# STM32F103C8T6-V2_0.net
KiCad netlist of a schematic drawn in EasyEDA Pro
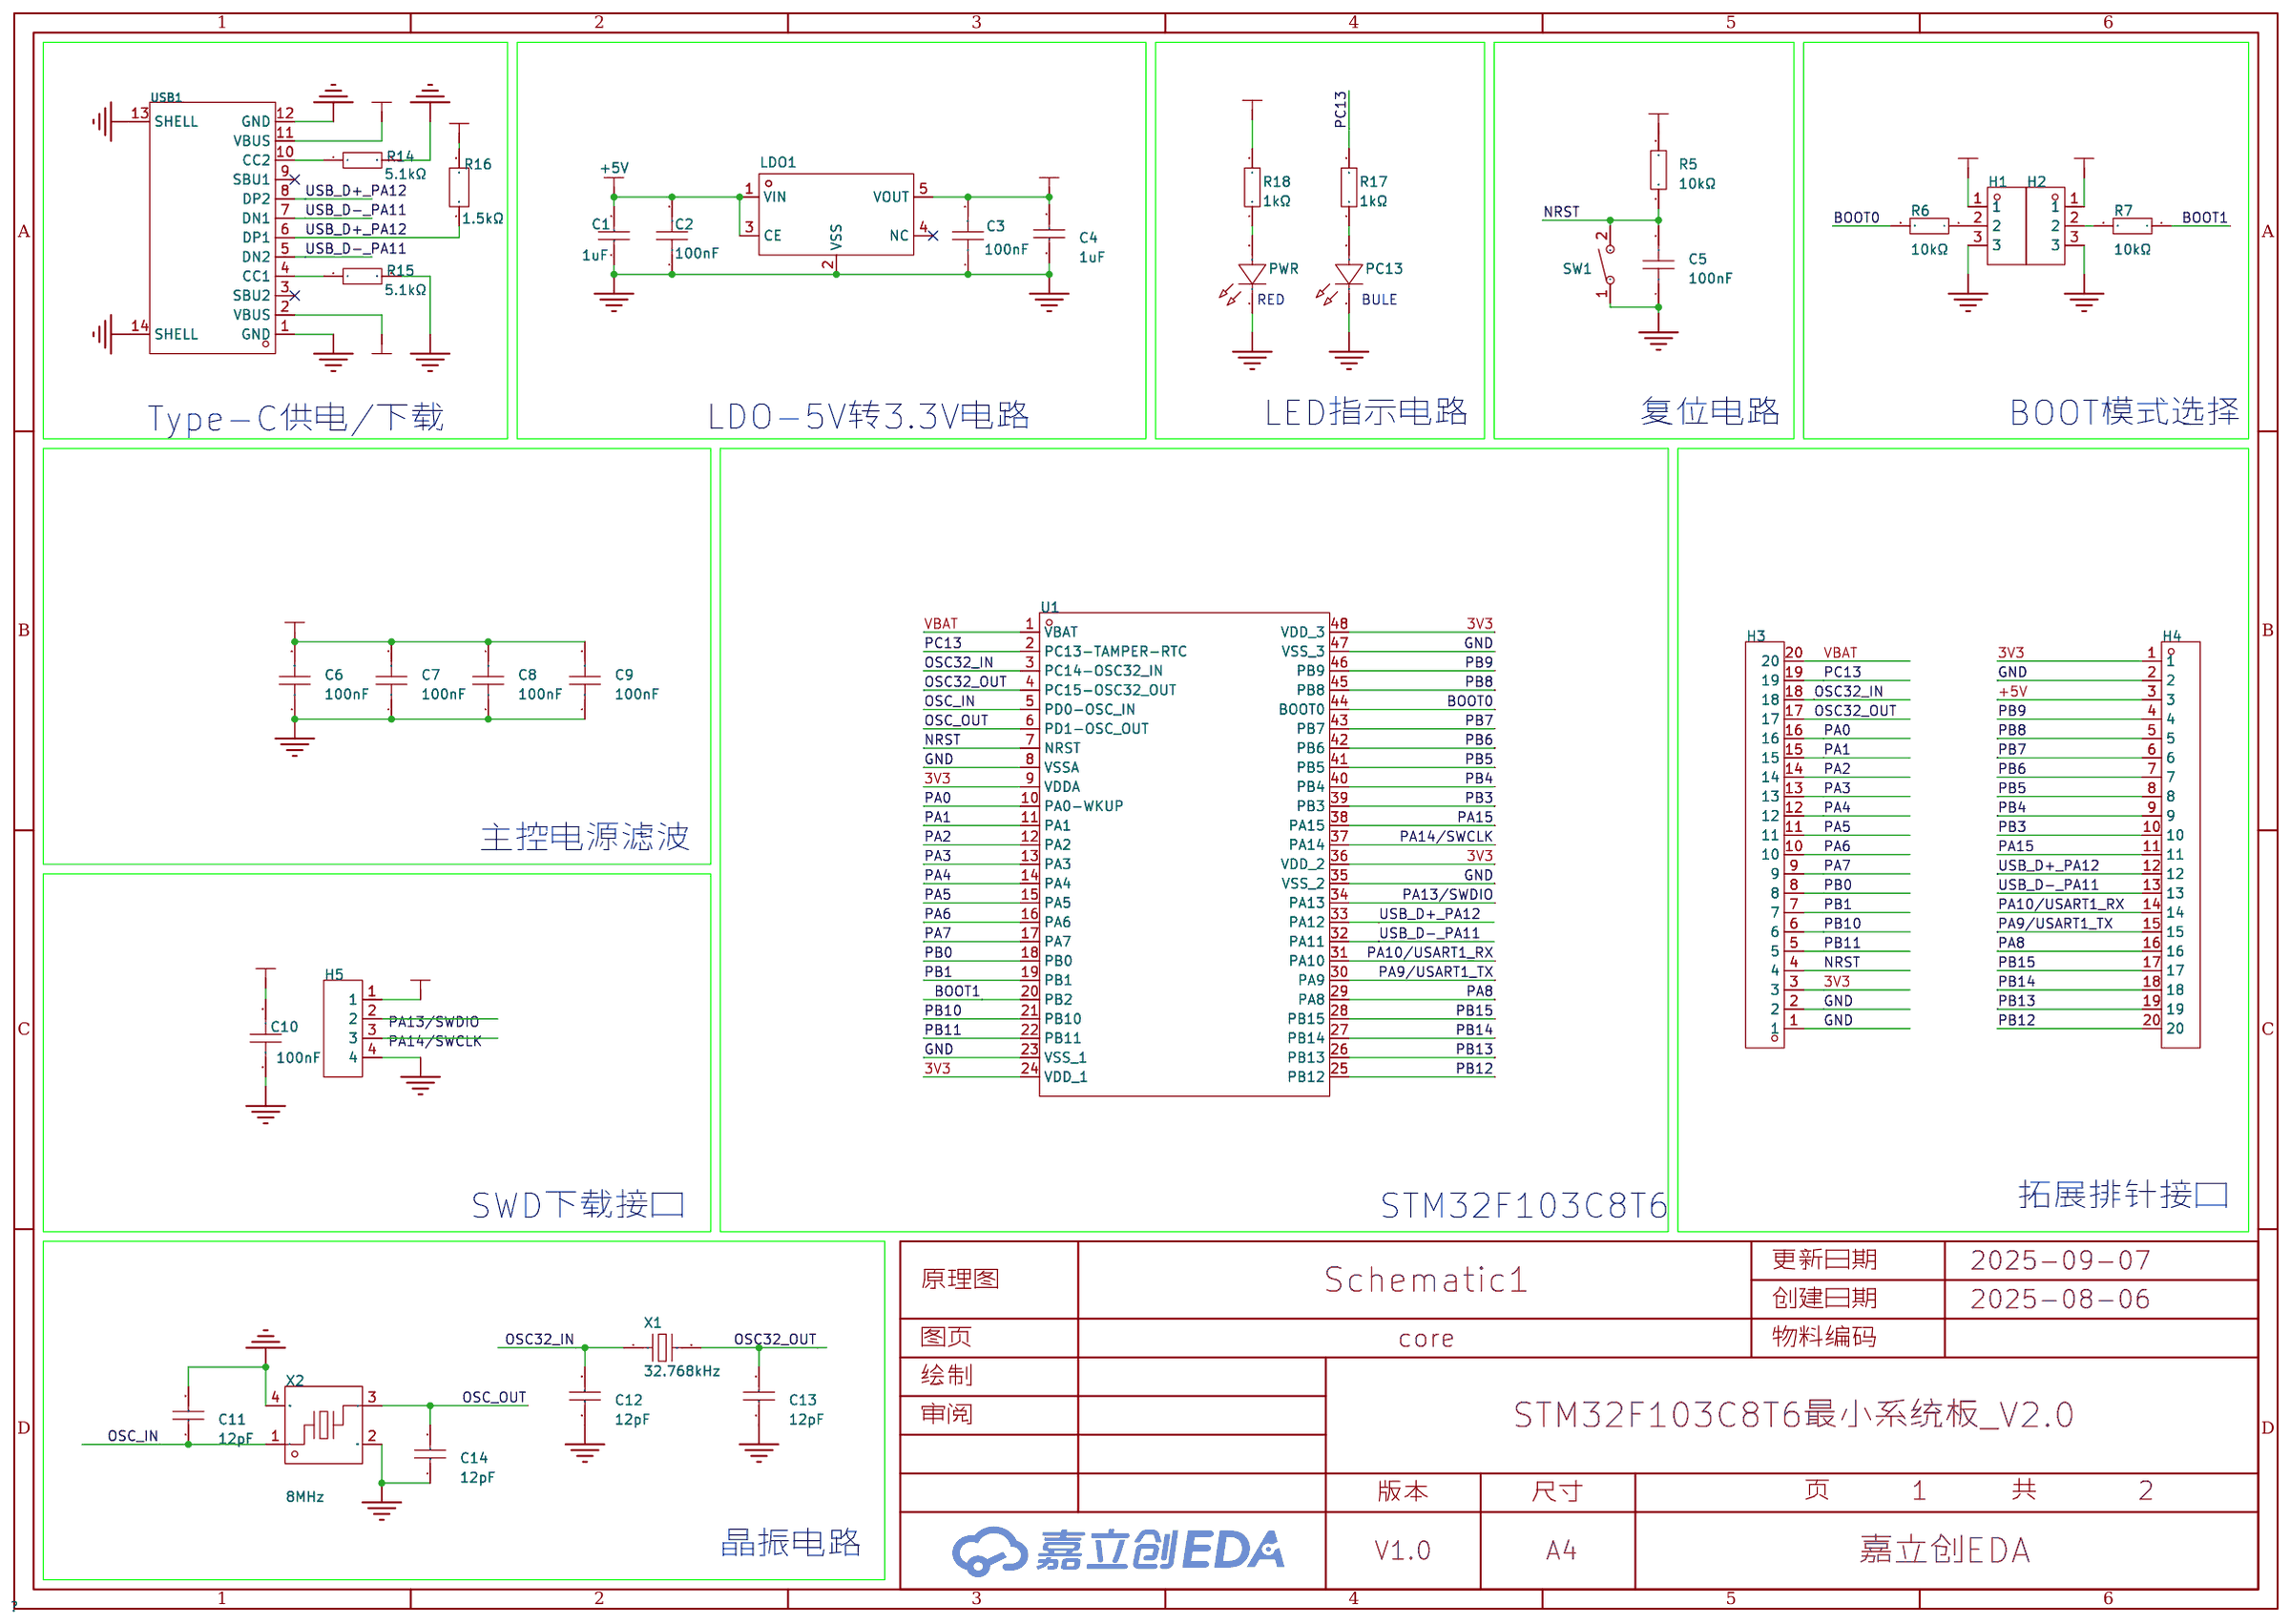
[diagram p0: core]
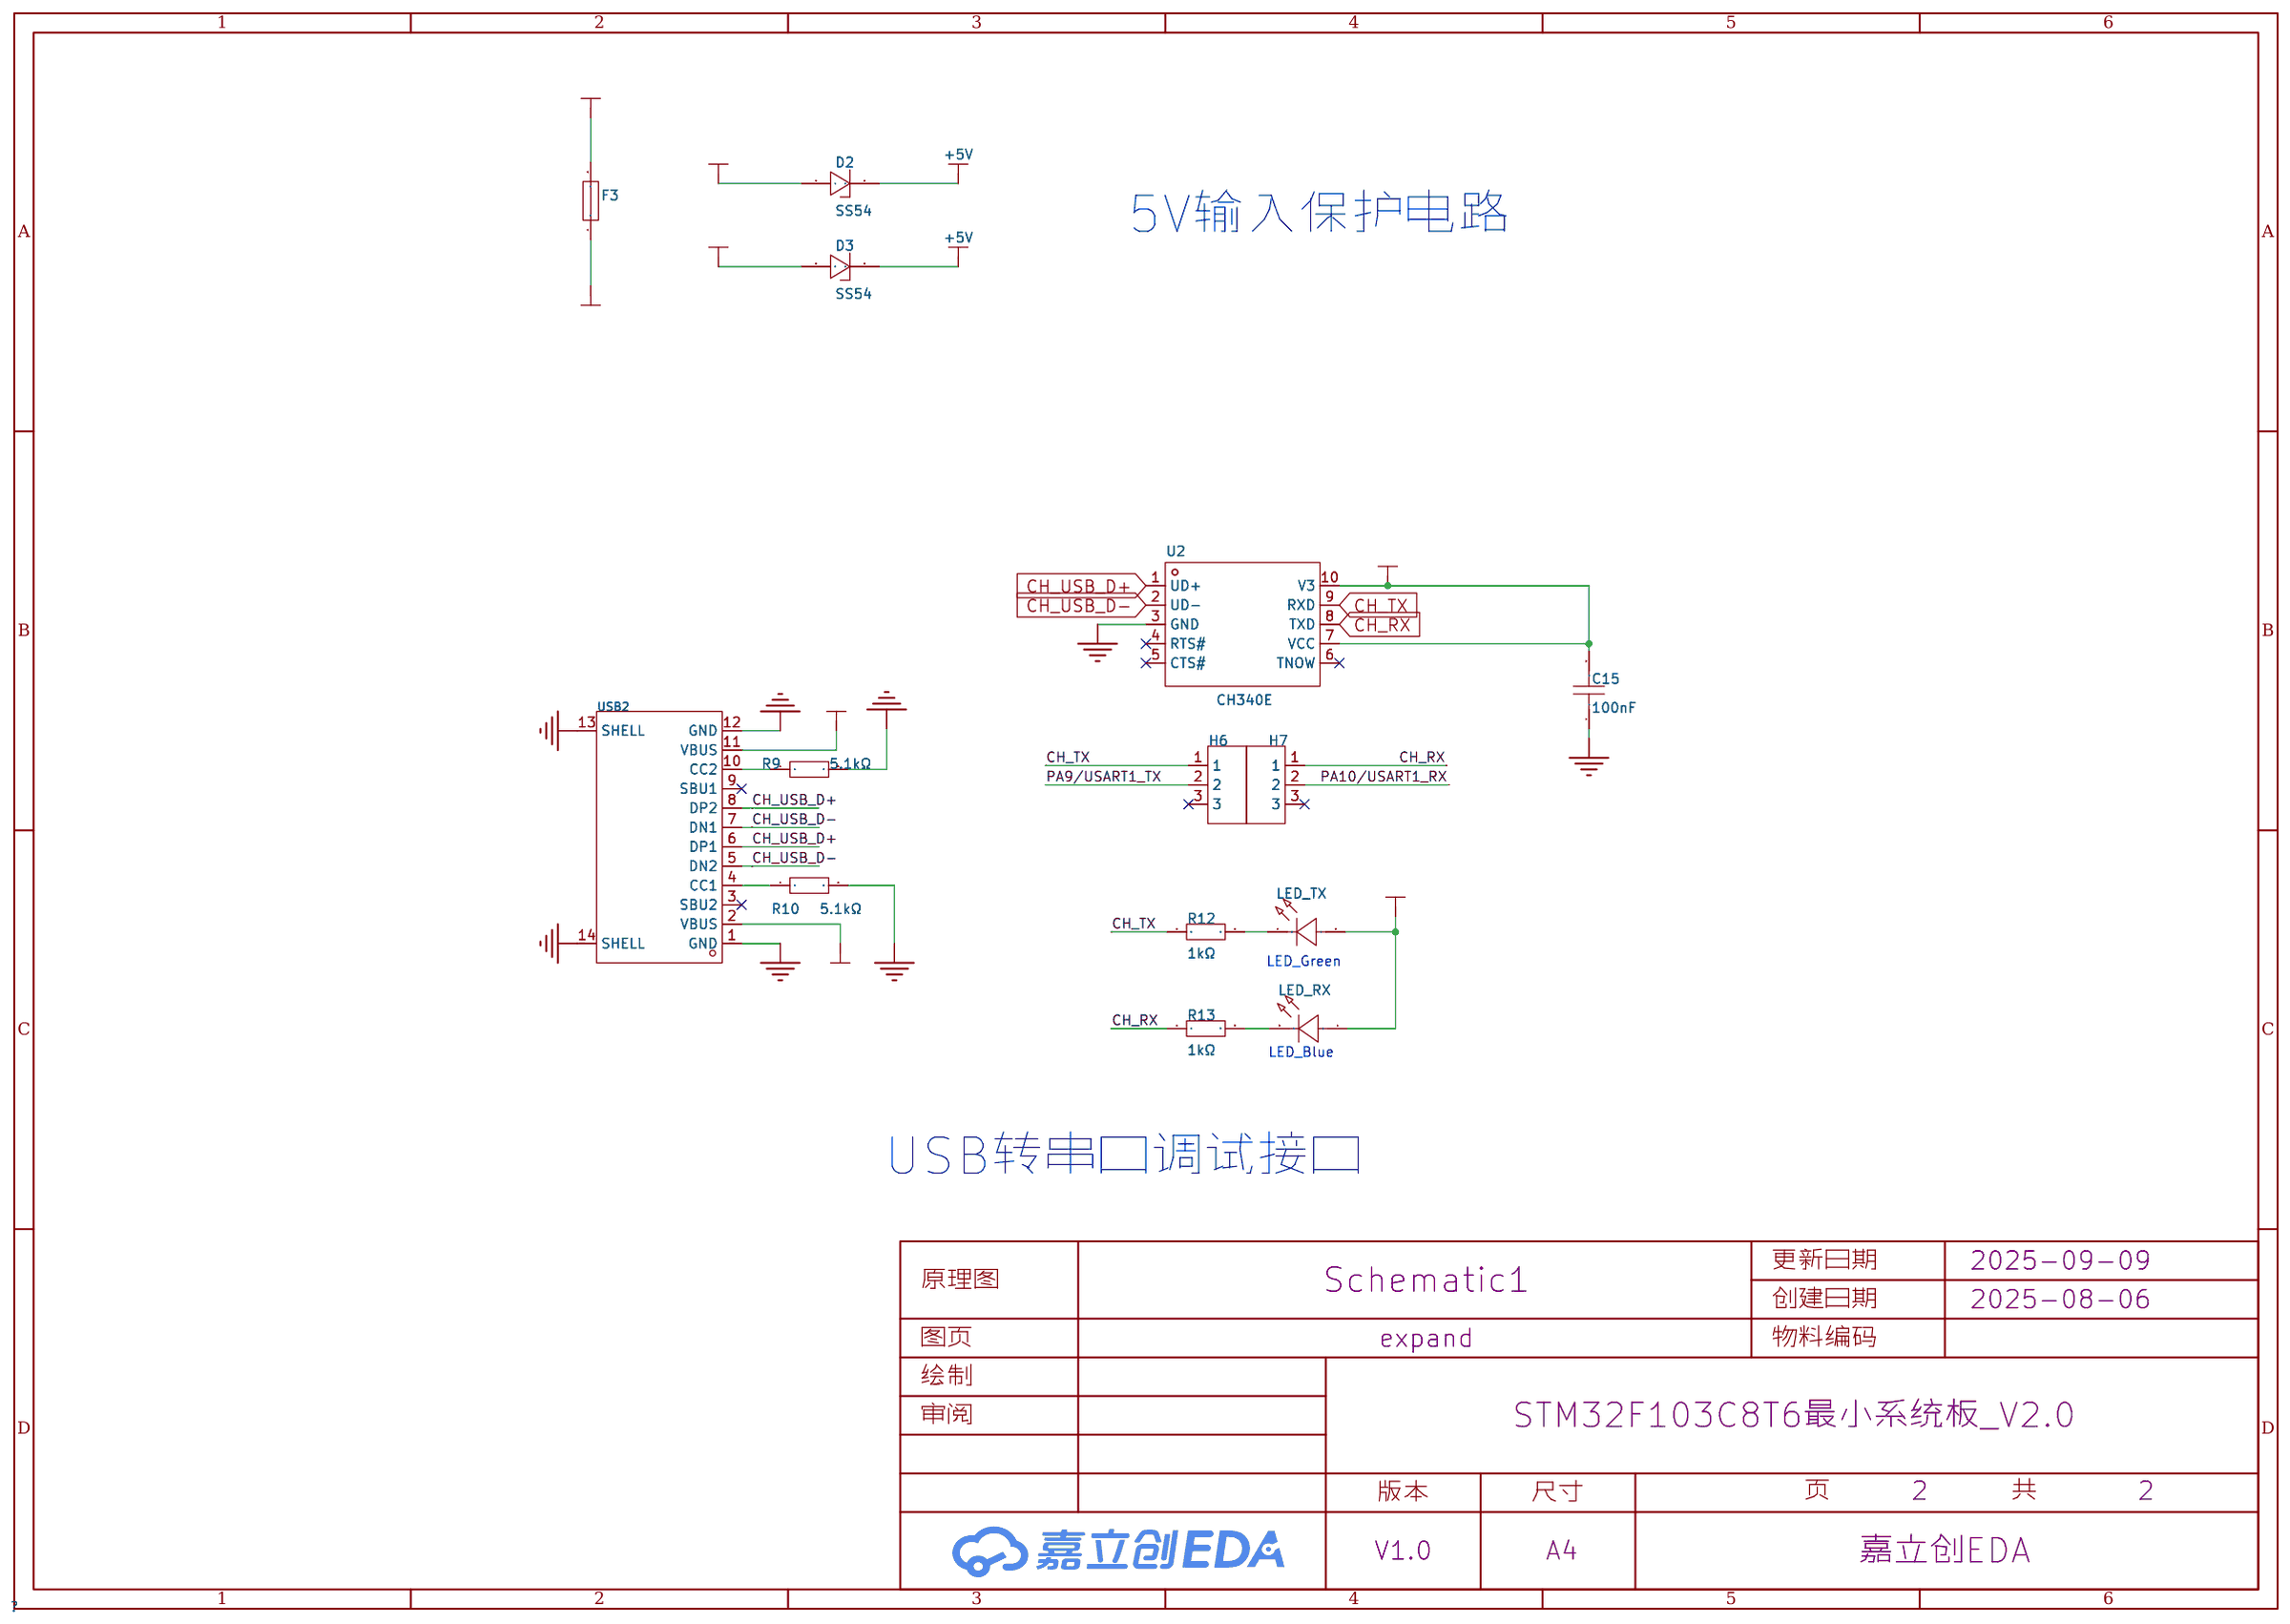
[diagram p1: expand]

(export (version "E")
  (design (tool "Eeschema 10.0.6"))
  (components
    (comp (ref "C1")
      (value "1uF")
      (footprint "easyedapro:C0402")
      (description "容值:1uF;精度:±10%;额定电压:10V;材质(温度系数):X5R;")
      (fields
        (field (name "Manufacturer Part") "CL21B105KBFNNNE")
        (field (name "Manufacturer") "SAMSUNG(三星)")
      )
      (libsource (lib "easyedapro") (part "CL05A105KP5NNNC"))
    )
    (comp (ref "C2")
      (value "100nF")
      (footprint "easyedapro:C0402")
      (description "容值:100nF;精度:±10%;额定电压:50V;材质(温度系数):X7R;")
      (fields
        (field (name "Manufacturer Part") "CC0805KRX7R9BB104")
        (field (name "Manufacturer") "YAGEO(国巨)")
      )
      (libsource (lib "easyedapro") (part "GRM155R71H104KE14D"))
    )
    (comp (ref "C3")
      (value "100nF")
      (footprint "easyedapro:C0402")
      (description "容值:100nF;精度:±10%;额定电压:50V;材质(温度系数):X7R;")
      (fields
        (field (name "Manufacturer Part") "CC0805KRX7R9BB104")
        (field (name "Manufacturer") "YAGEO(国巨)")
      )
      (libsource (lib "easyedapro") (part "GRM155R71H104KE14D"))
    )
    (comp (ref "C4")
      (value "1uF")
      (footprint "easyedapro:C0402")
      (description "容值:1uF;精度:±10%;额定电压:10V;材质(温度系数):X5R;")
      (fields
        (field (name "Manufacturer Part") "CL21B105KBFNNNE")
        (field (name "Manufacturer") "SAMSUNG(三星)")
      )
      (libsource (lib "easyedapro") (part "CL05A105KP5NNNC"))
    )
    (comp (ref "C5")
      (value "100nF")
      (footprint "easyedapro:C0402")
      (description "容值:100nF;精度:±10%;额定电压:50V;材质(温度系数):X7R;")
      (fields
        (field (name "Manufacturer Part") "CC0805KRX7R9BB104")
        (field (name "Manufacturer") "YAGEO(国巨)")
      )
      (libsource (lib "easyedapro") (part "GRM155R71H104KE14D"))
    )
    (comp (ref "C6")
      (value "100nF")
      (footprint "easyedapro:C0402")
      (description "容值:100nF;精度:±10%;额定电压:50V;材质(温度系数):X7R;")
      (fields
        (field (name "Manufacturer Part") "CC0805KRX7R9BB104")
        (field (name "Manufacturer") "YAGEO(国巨)")
      )
      (libsource (lib "easyedapro") (part "GRM155R71H104KE14D"))
    )
    (comp (ref "C7")
      (value "100nF")
      (footprint "easyedapro:C0402")
      (description "容值:100nF;精度:±10%;额定电压:50V;材质(温度系数):X7R;")
      (fields
        (field (name "Manufacturer Part") "CC0805KRX7R9BB104")
        (field (name "Manufacturer") "YAGEO(国巨)")
      )
      (libsource (lib "easyedapro") (part "GRM155R71H104KE14D"))
    )
    (comp (ref "C8")
      (value "100nF")
      (footprint "easyedapro:C0402")
      (description "容值:100nF;精度:±10%;额定电压:50V;材质(温度系数):X7R;")
      (fields
        (field (name "Manufacturer Part") "CC0805KRX7R9BB104")
        (field (name "Manufacturer") "YAGEO(国巨)")
      )
      (libsource (lib "easyedapro") (part "GRM155R71H104KE14D"))
    )
    (comp (ref "C9")
      (value "100nF")
      (footprint "easyedapro:C0402")
      (description "容值:100nF;精度:±10%;额定电压:50V;材质(温度系数):X7R;")
      (fields
        (field (name "Manufacturer Part") "CC0805KRX7R9BB104")
        (field (name "Manufacturer") "YAGEO(国巨)")
      )
      (libsource (lib "easyedapro") (part "GRM155R71H104KE14D"))
    )
    (comp (ref "C10")
      (value "100nF")
      (footprint "easyedapro:C0402")
      (description "容值:100nF;精度:±10%;额定电压:50V;材质(温度系数):X7R;")
      (fields
        (field (name "Manufacturer Part") "CC0805KRX7R9BB104")
        (field (name "Manufacturer") "YAGEO(国巨)")
      )
      (libsource (lib "easyedapro") (part "GRM155R71H104KE14D"))
    )
    (comp (ref "C11")
      (value "12pF")
      (footprint "easyedapro:C0402")
      (description "容值:12pF;精度:±5%;额定电压:50V;材质(温度系数):C0G;")
      (fields (field (name "Manufacturer Part") "0402CG120J500NT") (field (name "Manufacturer") "FH(风华)"))
      (libsource (lib "easyedapro") (part "0402CG120J500NT"))
    )
    (comp (ref "C12")
      (value "12pF")
      (footprint "easyedapro:C0402")
      (description "容值:12pF;精度:±5%;额定电压:50V;材质(温度系数):C0G;")
      (fields (field (name "Manufacturer Part") "0402CG120J500NT") (field (name "Manufacturer") "FH(风华)"))
      (libsource (lib "easyedapro") (part "0402CG120J500NT"))
    )
    (comp (ref "C13")
      (value "12pF")
      (footprint "easyedapro:C0402")
      (description "容值:12pF;精度:±5%;额定电压:50V;材质(温度系数):C0G;")
      (fields (field (name "Manufacturer Part") "0402CG120J500NT") (field (name "Manufacturer") "FH(风华)"))
      (libsource (lib "easyedapro") (part "0402CG120J500NT"))
    )
    (comp (ref "C14")
      (value "12pF")
      (footprint "easyedapro:C0402")
      (description "容值:12pF;精度:±5%;额定电压:50V;材质(温度系数):C0G;")
      (fields (field (name "Manufacturer Part") "0402CG120J500NT") (field (name "Manufacturer") "FH(风华)"))
      (libsource (lib "easyedapro") (part "0402CG120J500NT"))
    )
    (comp (ref "H1")
      (value "PZ254V-11-03P")
      (footprint "easyedapro:HDR-TH_3P-P2.54-V-M")
      (fields (field (name "Manufacturer") "XFCN(兴飞)"))
      (libsource (lib "easyedapro") (part "PZ254V-11-03P_C2937625"))
    )
    (comp (ref "H2")
      (value "PZ254V-11-03P")
      (footprint "easyedapro:HDR-TH_3P-P2.54-V-M")
      (fields (field (name "Manufacturer") "XFCN(兴飞)"))
      (libsource (lib "easyedapro") (part "PZ254V-11-03P_C2937625"))
    )
    (comp (ref "H3")
      (value "PH2.54-01-20PZD")
      (footprint "easyedapro:HDR-TH_20P-P2.54-V-M-1")
      (fields (field (name "Manufacturer") "XUNPU(讯普)"))
      (libsource (lib "easyedapro") (part "HDR_2.54-1x20P"))
    )
    (comp (ref "H4")
      (value "PH2.54-01-20PZD")
      (footprint "easyedapro:HDR-TH_20P-P2.54-V-M-1")
      (fields (field (name "Manufacturer") "XUNPU(讯普)"))
      (libsource (lib "easyedapro") (part "HDR_2.54-1x20P"))
    )
    (comp (ref "H5")
      (value "PZ2.54-1*4-WZ")
      (footprint "easyedapro:HDR-TH_4P-P2.54-H-M-W7.7-P")
      (description "插针结构:1x4P;间距:2.54mm;安装方式:弯插;排数:单排;总PIN位数:4P;触头镀层:金;")
      (fields (field (name "Manufacturer") "ZHOURI(洲日)"))
      (libsource (lib "easyedapro") (part "PZ2.54-1*4-WZ"))
    )
    (comp (ref "LDO1")
      (value "ME6211C33M5G-N")
      (footprint "easyedapro:SOT-23-5_L3.0-W1.7-P0.95-LS2.8-BL")
      (description "输出类型:固定;输出极性:正;最大输入电压:6V;输出电压:3.3V;输出电流:500mA;电源纹波抑制比(PSRR):70dB;")
      (fields (field (name "Manufacturer") "MICRONE(南京微盟)"))
      (libsource (lib "easyedapro") (part "ME6211C33M5G-N"))
    )
    (comp (ref "PC13")
      (value "XL-2012UBC")
      (footprint "easyedapro:LED0805-RD")
      (fields (field (name "Manufacturer") "XINGLIGHT(成兴光)"))
      (libsource (lib "easyedapro") (part "XL-2012UBC"))
    )
    (comp (ref "PWR")
      (value "XL-2012SURC")
      (footprint "easyedapro:LED0805-RD_RED")
      (description "发光颜色:红色;功率:55mW;正向电流:25mA;主波长:617nm~621nm;透镜颜色:无色透明透镜;色温:-;发光角度:120°;载带方式:正贴;工作温度:-30°C~+85°C;")
      (fields (field (name "Manufacturer") "XINGLIGHT(成兴光)"))
      (libsource (lib "easyedapro") (part "XL-2012SURC"))
    )
    (comp (ref "R5")
      (value "10kΩ")
      (footprint "easyedapro:R0402")
      (description "电阻类型:厚膜电阻;阻值:10kΩ;精度:±1%;功率:62.5mW;最大工作电压:50V;温度系数:±100ppm/°C;")
      (fields
        (field (name "Manufacturer Part") "0805W8F1002T5E")
        (field (name "Manufacturer") "UNI-ROYAL(厚声)")
      )
      (libsource (lib "easyedapro") (part "RC0402FR-0710KL"))
    )
    (comp (ref "R6")
      (value "10kΩ")
      (footprint "easyedapro:R0402")
      (description "电阻类型:厚膜电阻;阻值:10kΩ;精度:±1%;功率:62.5mW;最大工作电压:50V;温度系数:±100ppm/°C;")
      (fields
        (field (name "Manufacturer Part") "0805W8F1002T5E")
        (field (name "Manufacturer") "UNI-ROYAL(厚声)")
      )
      (libsource (lib "easyedapro") (part "RC0402FR-0710KL"))
    )
    (comp (ref "R7")
      (value "10kΩ")
      (footprint "easyedapro:R0402")
      (description "电阻类型:厚膜电阻;阻值:10kΩ;精度:±1%;功率:62.5mW;最大工作电压:50V;温度系数:±100ppm/°C;")
      (fields
        (field (name "Manufacturer Part") "0805W8F1002T5E")
        (field (name "Manufacturer") "UNI-ROYAL(厚声)")
      )
      (libsource (lib "easyedapro") (part "RC0402FR-0710KL"))
    )
    (comp (ref "R14")
      (value "5.1kΩ")
      (footprint "easyedapro:R0805")
      (description "电阻类型:厚膜电阻;阻值:5.1kΩ;精度:±1%;功率:125mW;最大工作电压:150V;温度系数:±100ppm/°C;")
      (fields
        (field (name "Manufacturer Part") "0805W8F5101T5E")
        (field (name "Manufacturer") "UNI-ROYAL(厚声)")
      )
      (libsource (lib "easyedapro") (part "0805W8F5101T5E"))
    )
    (comp (ref "R15")
      (value "5.1kΩ")
      (footprint "easyedapro:R0805")
      (description "电阻类型:厚膜电阻;阻值:5.1kΩ;精度:±1%;功率:125mW;最大工作电压:150V;温度系数:±100ppm/°C;")
      (fields
        (field (name "Manufacturer Part") "0805W8F5101T5E")
        (field (name "Manufacturer") "UNI-ROYAL(厚声)")
      )
      (libsource (lib "easyedapro") (part "0805W8F5101T5E"))
    )
    (comp (ref "R16")
      (value "1.5kΩ")
      (footprint "easyedapro:R0805")
      (description "电阻类型:厚膜电阻;阻值:1.5kΩ;精度:±1%;功率:125mW;工作电压:150V;温度系数:±100ppm/°C;")
      (fields (field (name "Manufacturer Part") "FRC0805F1501TS") (field (name "Manufacturer") "FOJAN(富捷)"))
      (libsource (lib "easyedapro") (part "FRC0805F1501TS"))
    )
    (comp (ref "R17")
      (value "1kΩ")
      (footprint "easyedapro:R0805")
      (description "电阻类型:厚膜电阻;阻值:1kΩ;精度:±1%;功率:125mW;最大工作电压:150V;温度系数:±100ppm/°C;")
      (fields
        (field (name "Manufacturer Part") "0805W8F1001T5E")
        (field (name "Manufacturer") "UNI-ROYAL(厚声)")
      )
      (libsource (lib "easyedapro") (part "0805W8F1001T5E"))
    )
    (comp (ref "R18")
      (value "1kΩ")
      (footprint "easyedapro:R0805")
      (description "电阻类型:厚膜电阻;阻值:1kΩ;精度:±1%;功率:125mW;最大工作电压:150V;温度系数:±100ppm/°C;")
      (fields
        (field (name "Manufacturer Part") "0805W8F1001T5E")
        (field (name "Manufacturer") "UNI-ROYAL(厚声)")
      )
      (libsource (lib "easyedapro") (part "0805W8F1001T5E"))
    )
    (comp (ref "SW1")
      (value "TS-1101-B-W")
      (footprint "easyedapro:KEY-SMD_2P-L6.0-W3.6-P7.4-LS8.0-L")
      (description "触点电流:50mA;额定电压(DC):12V;绝缘电阻:-;电路结构:单刀单掷;安装方式:立贴;带灯:无;作用力:160gf;机械寿命:5万次;带支架:否;")
      (fields (field (name "Manufacturer") "XKB Connectivity(中国星坤)"))
      (libsource (lib "easyedapro") (part "TS-1101-B-W"))
    )
    (comp (ref "U1")
      (value "STM32F103C8T6")
      (fields (field (name "Manufacturer") "ST(意法半导体)"))
      (libsource (lib "easyedapro") (part "STM32F103C8T6"))
    )
    (comp (ref "USB1")
      (value "TYPE-C 16PIN 2MD(073)")
      (footprint "easyedapro:USB-C-SMD_TYPE-C-6PIN-2MD-073")
      (description "连接器类型:Type-C;标准:-;公母:母座;触点数量:16;端口数量:1;安装方式:卧贴;额定电流 - 电源:5A;工作温度范围:-25°C~+85°C;")
      (fields (field (name "Manufacturer") "SHOU HAN(首韩)"))
      (libsource (lib "easyedapro") (part "TYPE-C 16PIN 2MD(073)"))
    )
    (comp (ref "X1")
      (value "32.768kHz")
      (footprint "easyedapro:OSC-SMD_L3.2-W1.5")
      (description "晶振类型:贴片晶振;频率:32.768kHz;常温频差:±20ppm;外接负载电容:12.5pF;频率稳定度(全温):-;")
      (fields (field (name "Manufacturer Part") "X321532768KGD2SI") (field (name "Manufacturer") "YXC(扬兴晶振)"))
      (libsource (lib "easyedapro") (part "X321532768KGD2SI"))
    )
    (comp (ref "X2")
      (value "8MHz")
      (footprint "easyedapro:CRYSTAL-SMD_4P-L3.2-W2.5-BL-1")
      (description "晶振类型:贴片晶振;频率:8MHz;常温频差:±10ppm;外接负载电容:12pF;频率稳定度(全温):±20ppm;")
      (fields
        (field (name "Manufacturer Part") "XL2EL89COI-111YLC-8M")
        (field (name "Manufacturer") "YXC(扬兴晶振)")
      )
      (libsource (lib "easyedapro") (part "XL2EL89COI-111YLC-8M"))
    )
    (comp (ref "C15")
      (value "100nF")
      (footprint "easyedapro:C0402")
      (description "容值:100nF;精度:±10%;额定电压:50V;材质(温度系数):X7R;")
      (fields
        (field (name "Manufacturer Part") "CC0805KRX7R9BB104")
        (field (name "Manufacturer") "YAGEO(国巨)")
      )
      (libsource (lib "easyedapro") (part "GRM155R71H104KE14D"))
    )
    (comp (ref "D2")
      (value "SS54")
      (footprint "easyedapro:SMA_L4.3-W2.6-LS5.0-FD")
      (description "二极管配置:独立式;正向压降(Vf):550mV@5.0A;直流反向耐压(Vr):40V;整流电流:5A;")
      (fields (field (name "Manufacturer") "R+O(宏嘉诚)"))
      (libsource (lib "easyedapro") (part "SS54_C7420369"))
    )
    (comp (ref "D3")
      (value "SS54")
      (footprint "easyedapro:SMA_L4.3-W2.6-LS5.0-FD")
      (description "二极管配置:独立式;正向压降(Vf):550mV@5.0A;直流反向耐压(Vr):40V;整流电流:5A;")
      (fields (field (name "Manufacturer") "R+O(宏嘉诚)"))
      (libsource (lib "easyedapro") (part "SS54_C7420369"))
    )
    (comp (ref "F3")
      (value "BSMD0805-050-6V")
      (footprint "easyedapro:F0603")
      (description "最大电压:6V;最大电流:40A;保持电流:500mA;跳闸电流:1A;")
      (fields (field (name "Manufacturer") "BHFUSE(佰宏)"))
      (libsource (lib "easyedapro") (part "BSMD0603-050-6V"))
    )
    (comp (ref "H6")
      (value "PZ254V-11-03P")
      (footprint "easyedapro:HDR-TH_3P-P2.54-V-M")
      (fields (field (name "Manufacturer") "XFCN(兴飞)"))
      (libsource (lib "easyedapro") (part "PZ254V-11-03P_C2937625"))
    )
    (comp (ref "H7")
      (value "PZ254V-11-03P")
      (footprint "easyedapro:HDR-TH_3P-P2.54-V-M")
      (fields (field (name "Manufacturer") "XFCN(兴飞)"))
      (libsource (lib "easyedapro") (part "PZ254V-11-03P_C2937625"))
    )
    (comp (ref "LED_RX")
      (value "XL-1608UBC-06A")
      (footprint "easyedapro:LED0603-R-RD")
      (fields (field (name "Manufacturer") "XINGLIGHT(成兴光)"))
      (libsource (lib "easyedapro") (part "XL-1608UBC-06A"))
    )
    (comp (ref "LED_TX")
      (value "XL-1608PGC-06")
      (footprint "easyedapro:LED0603-RD_GREEN")
      (fields (field (name "Manufacturer") "XINGLIGHT(成兴光)"))
      (libsource (lib "easyedapro") (part "XL-1608PGC-06"))
    )
    (comp (ref "R9")
      (value "5.1kΩ")
      (footprint "easyedapro:R0402")
      (description "电阻类型:厚膜电阻;阻值:5.1kΩ;精度:±1%;功率:62.5mW;最大工作电压:50V;温度系数:±100ppm/°C;")
      (fields
        (field (name "Manufacturer Part") "0805W8F5101T5E")
        (field (name "Manufacturer") "UNI-ROYAL(厚声)")
      )
      (libsource (lib "easyedapro") (part "0402WGF5101TCE"))
    )
    (comp (ref "R10")
      (value "5.1kΩ")
      (footprint "easyedapro:R0402")
      (description "电阻类型:厚膜电阻;阻值:5.1kΩ;精度:±1%;功率:62.5mW;最大工作电压:50V;温度系数:±100ppm/°C;")
      (fields
        (field (name "Manufacturer Part") "0805W8F5101T5E")
        (field (name "Manufacturer") "UNI-ROYAL(厚声)")
      )
      (libsource (lib "easyedapro") (part "0402WGF5101TCE"))
    )
    (comp (ref "R12")
      (value "1kΩ")
      (footprint "easyedapro:R0402")
      (description "电阻类型:厚膜电阻;阻值:1kΩ;精度:±1%;功率:62.5mW;最大工作电压:50V;温度系数:±100ppm/°C;")
      (fields
        (field (name "Manufacturer Part") "0805W8F1001T5E")
        (field (name "Manufacturer") "UNI-ROYAL(厚声)")
      )
      (libsource (lib "easyedapro") (part "0402WGF1001TCE"))
    )
    (comp (ref "R13")
      (value "1kΩ")
      (footprint "easyedapro:R0402")
      (description "电阻类型:厚膜电阻;阻值:1kΩ;精度:±1%;功率:62.5mW;最大工作电压:50V;温度系数:±100ppm/°C;")
      (fields
        (field (name "Manufacturer Part") "0805W8F1001T5E")
        (field (name "Manufacturer") "UNI-ROYAL(厚声)")
      )
      (libsource (lib "easyedapro") (part "0402WGF1001TCE"))
    )
    (comp (ref "U2")
      (value "CH340E")
      (footprint "easyedapro:MSOP-10_L3.0-W3.0-P0.50-LS5.0-BL")
      (description "应用功能:收发器;接口协议:USB 2.0;数据速率:2Mbps;")
      (fields (field (name "Manufacturer") "WCH(南京沁恒)"))
      (libsource (lib "easyedapro") (part "CH340E"))
    )
    (comp (ref "USB2")
      (value "TYPE-C 16PIN 2MD(073)")
      (footprint "easyedapro:USB-C-SMD_TYPE-C-6PIN-2MD-073")
      (description "连接器类型:Type-C;标准:-;公母:母座;触点数量:16;端口数量:1;安装方式:卧贴;额定电流 - 电源:5A;工作温度范围:-25°C~+85°C;")
      (fields (field (name "Manufacturer") "SHOU HAN(首韩)"))
      (libsource (lib "easyedapro") (part "TYPE-C 16PIN 2MD(073)"))
    )
  )
  (nets
    (net (code "1") (name "+5V") (class "Default")
      (node (ref "C1") (pin "2") (pinfunction "2_2") (pintype "input"))
      (node (ref "C2") (pin "2") (pinfunction "2_2") (pintype "unspecified"))
      (node (ref "D2") (pin "2") (pinfunction "K_2") (pintype "unspecified"))
      (node (ref "D3") (pin "2") (pinfunction "K_2") (pintype "unspecified"))
      (node (ref "H4") (pin "3") (pinfunction "3_3") (pintype "input"))
      (node (ref "LDO1") (pin "1") (pinfunction "VIN_1") (pintype "input"))
      (node (ref "LDO1") (pin "3") (pinfunction "CE_3") (pintype "input"))
    )
    (net (code "2") (name "3V3") (class "Default")
      (node (ref "C10") (pin "2") (pinfunction "2_2") (pintype "unspecified"))
      (node (ref "C15") (pin "2") (pinfunction "2_2") (pintype "unspecified"))
      (node (ref "C3") (pin "2") (pinfunction "2_2") (pintype "unspecified"))
      (node (ref "C4") (pin "2") (pinfunction "2_2") (pintype "input"))
      (node (ref "C6") (pin "2") (pinfunction "2_2") (pintype "unspecified"))
      (node (ref "C7") (pin "2") (pinfunction "2_2") (pintype "unspecified"))
      (node (ref "C8") (pin "2") (pinfunction "2_2") (pintype "unspecified"))
      (node (ref "C9") (pin "2") (pinfunction "2_2") (pintype "unspecified"))
      (node (ref "H1") (pin "1") (pinfunction "1_1") (pintype "input"))
      (node (ref "H2") (pin "1") (pinfunction "1_1") (pintype "input"))
      (node (ref "H3") (pin "3") (pinfunction "3_3") (pintype "input"))
      (node (ref "H4") (pin "1") (pinfunction "1_1") (pintype "input"))
      (node (ref "H5") (pin "1") (pinfunction "1_1") (pintype "unspecified"))
      (node (ref "LDO1") (pin "5") (pinfunction "VOUT_5") (pintype "input"))
      (node (ref "LED_RX") (pin "1") (pinfunction "A_1") (pintype "unspecified"))
      (node (ref "LED_TX") (pin "2") (pinfunction "A_2") (pintype "unspecified"))
      (node (ref "R16") (pin "2") (pinfunction "2_2") (pintype "unspecified"))
      (node (ref "R18") (pin "2") (pinfunction "2_2") (pintype "input"))
      (node (ref "R5") (pin "2") (pinfunction "2_2") (pintype "input"))
      (node (ref "U1") (pin "24") (pinfunction "VDD_1_24") (pintype "unspecified"))
      (node (ref "U1") (pin "36") (pinfunction "VDD_2_36") (pintype "unspecified"))
      (node (ref "U1") (pin "48") (pinfunction "VDD_3_48") (pintype "unspecified"))
      (node (ref "U1") (pin "9") (pinfunction "VDDA_9") (pintype "unspecified"))
      (node (ref "U2") (pin "10") (pinfunction "V3_10") (pintype "input"))
      (node (ref "U2") (pin "7") (pinfunction "VCC_7") (pintype "input"))
    )
    (net (code "3") (name "BOOT0") (class "Default")
      (node (ref "R6") (pin "2") (pinfunction "2_2") (pintype "input"))
      (node (ref "U1") (pin "44") (pinfunction "BOOT0_44") (pintype "unspecified"))
    )
    (net (code "4") (name "BOOT1") (class "Default")
      (node (ref "R7") (pin "1") (pinfunction "1_1") (pintype "input"))
      (node (ref "U1") (pin "20") (pinfunction "PB2_20") (pintype "unspecified"))
    )
    (net (code "5") (name "CH_RX") (class "Default")
      (node (ref "H7") (pin "1") (pinfunction "1_1") (pintype "unspecified"))
      (node (ref "R13") (pin "1") (pinfunction "1_1") (pintype "input"))
      (node (ref "U2") (pin "8") (pinfunction "TXD_8") (pintype "input"))
    )
    (net (code "6") (name "CH_TX") (class "Default")
      (node (ref "H6") (pin "1") (pinfunction "1_1") (pintype "unspecified"))
      (node (ref "R12") (pin "1") (pinfunction "1_1") (pintype "input"))
      (node (ref "U2") (pin "9") (pinfunction "RXD_9") (pintype "input"))
    )
    (net (code "7") (name "CH_USB_D+") (class "Default")
      (node (ref "U2") (pin "1") (pinfunction "UD+_1") (pintype "input"))
      (node (ref "USB2") (pin "6") (pinfunction "DP1_6") (pintype "input"))
      (node (ref "USB2") (pin "8") (pinfunction "DP2_8") (pintype "input"))
    )
    (net (code "8") (name "CH_USB_D-") (class "Default")
      (node (ref "U2") (pin "2") (pinfunction "UD-_2") (pintype "input"))
      (node (ref "USB2") (pin "5") (pinfunction "DN2_5") (pintype "input"))
      (node (ref "USB2") (pin "7") (pinfunction "DN1_7") (pintype "input"))
    )
    (net (code "9") (name "GND") (class "Default")
      (node (ref "C1") (pin "1") (pinfunction "1_1") (pintype "input"))
      (node (ref "C10") (pin "1") (pinfunction "1_1") (pintype "unspecified"))
      (node (ref "C11") (pin "2") (pinfunction "2_2") (pintype "input"))
      (node (ref "C12") (pin "1") (pinfunction "1_1") (pintype "input"))
      (node (ref "C13") (pin "1") (pinfunction "1_1") (pintype "input"))
      (node (ref "C14") (pin "1") (pinfunction "1_1") (pintype "input"))
      (node (ref "C15") (pin "1") (pinfunction "1_1") (pintype "unspecified"))
      (node (ref "C2") (pin "1") (pinfunction "1_1") (pintype "unspecified"))
      (node (ref "C3") (pin "1") (pinfunction "1_1") (pintype "unspecified"))
      (node (ref "C4") (pin "1") (pinfunction "1_1") (pintype "input"))
      (node (ref "C5") (pin "1") (pinfunction "1_1") (pintype "unspecified"))
      (node (ref "C6") (pin "1") (pinfunction "1_1") (pintype "unspecified"))
      (node (ref "C7") (pin "1") (pinfunction "1_1") (pintype "unspecified"))
      (node (ref "C8") (pin "1") (pinfunction "1_1") (pintype "unspecified"))
      (node (ref "C9") (pin "1") (pinfunction "1_1") (pintype "unspecified"))
      (node (ref "H1") (pin "3") (pinfunction "3_3") (pintype "input"))
      (node (ref "H2") (pin "3") (pinfunction "3_3") (pintype "input"))
      (node (ref "H3") (pin "1") (pinfunction "1_1") (pintype "input"))
      (node (ref "H3") (pin "2") (pinfunction "2_2") (pintype "input"))
      (node (ref "H4") (pin "2") (pinfunction "2_2") (pintype "input"))
      (node (ref "H5") (pin "4") (pinfunction "4_4") (pintype "unspecified"))
      (node (ref "LDO1") (pin "2") (pinfunction "VSS_2") (pintype "input"))
      (node (ref "PC13") (pin "1") (pinfunction "K_1") (pintype "unspecified"))
      (node (ref "PWR") (pin "1") (pinfunction "K_1") (pintype "unspecified"))
      (node (ref "R10") (pin "2") (pinfunction "2_2") (pintype "input"))
      (node (ref "R14") (pin "2") (pinfunction "2_2") (pintype "input"))
      (node (ref "R15") (pin "2") (pinfunction "2_2") (pintype "input"))
      (node (ref "R9") (pin "2") (pinfunction "2_2") (pintype "input"))
      (node (ref "SW1") (pin "1") (pinfunction "1_1") (pintype "input"))
      (node (ref "U1") (pin "23") (pinfunction "VSS_1_23") (pintype "unspecified"))
      (node (ref "U1") (pin "35") (pinfunction "VSS_2_35") (pintype "unspecified"))
      (node (ref "U1") (pin "47") (pinfunction "VSS_3_47") (pintype "unspecified"))
      (node (ref "U1") (pin "8") (pinfunction "VSSA_8") (pintype "unspecified"))
      (node (ref "U2") (pin "3") (pinfunction "GND_3") (pintype "input"))
      (node (ref "USB1") (pin "1") (pinfunction "GND_1") (pintype "input"))
      (node (ref "USB1") (pin "12") (pinfunction "GND_12") (pintype "input"))
      (node (ref "USB1") (pin "13") (pinfunction "SHELL_13") (pintype "input"))
      (node (ref "USB1") (pin "14") (pinfunction "SHELL_14") (pintype "input"))
      (node (ref "USB2") (pin "1") (pinfunction "GND_1") (pintype "input"))
      (node (ref "USB2") (pin "12") (pinfunction "GND_12") (pintype "input"))
      (node (ref "USB2") (pin "13") (pinfunction "SHELL_13") (pintype "input"))
      (node (ref "USB2") (pin "14") (pinfunction "SHELL_14") (pintype "input"))
      (node (ref "X2") (pin "2") (pinfunction "GND_2") (pintype "input"))
      (node (ref "X2") (pin "4") (pinfunction "GND_4") (pintype "input"))
    )
    (net (code "10") (name "IN_5V") (class "Default")
      (node (ref "D2") (pin "1") (pinfunction "A_1") (pintype "unspecified"))
      (node (ref "D3") (pin "1") (pinfunction "A_1") (pintype "unspecified"))
      (node (ref "F3") (pin "1") (pinfunction "1_1") (pintype "unspecified"))
    )
    (net (code "11") (name "NRST") (class "Default")
      (node (ref "C5") (pin "2") (pinfunction "2_2") (pintype "unspecified"))
      (node (ref "H3") (pin "4") (pinfunction "4_4") (pintype "input"))
      (node (ref "R5") (pin "1") (pinfunction "1_1") (pintype "input"))
      (node (ref "SW1") (pin "2") (pinfunction "2_2") (pintype "input"))
      (node (ref "U1") (pin "7") (pinfunction "NRST_7") (pintype "unspecified"))
    )
    (net (code "12") (name "Net-(H1-Pad2)") (class "Default")
      (node (ref "H1") (pin "2") (pinfunction "2_2") (pintype "input"))
      (node (ref "R6") (pin "1") (pinfunction "1_1") (pintype "input"))
    )
    (net (code "13") (name "Net-(H2-Pad2)") (class "Default")
      (node (ref "H2") (pin "2") (pinfunction "2_2") (pintype "input"))
      (node (ref "R7") (pin "2") (pinfunction "2_2") (pintype "input"))
    )
    (net (code "14") (name "Net-(LED_RX-K)") (class "Default")
      (node (ref "LED_RX") (pin "2") (pinfunction "K_2") (pintype "unspecified"))
      (node (ref "R13") (pin "2") (pinfunction "2_2") (pintype "input"))
    )
    (net (code "15") (name "Net-(LED_TX-K)") (class "Default")
      (node (ref "LED_TX") (pin "1") (pinfunction "K_1") (pintype "unspecified"))
      (node (ref "R12") (pin "2") (pinfunction "2_2") (pintype "input"))
    )
    (net (code "16") (name "Net-(PC13-A)") (class "Default")
      (node (ref "PC13") (pin "2") (pinfunction "A_2") (pintype "unspecified"))
      (node (ref "R17") (pin "1") (pinfunction "1_1") (pintype "input"))
    )
    (net (code "17") (name "Net-(PWR-A)") (class "Default")
      (node (ref "PWR") (pin "2") (pinfunction "A_2") (pintype "unspecified"))
      (node (ref "R18") (pin "1") (pinfunction "1_1") (pintype "input"))
    )
    (net (code "18") (name "Net-(USB1-CC1)") (class "Default")
      (node (ref "R15") (pin "1") (pinfunction "1_1") (pintype "input"))
      (node (ref "USB1") (pin "4") (pinfunction "CC1_4") (pintype "input"))
    )
    (net (code "19") (name "Net-(USB1-CC2)") (class "Default")
      (node (ref "R14") (pin "1") (pinfunction "1_1") (pintype "input"))
      (node (ref "USB1") (pin "10") (pinfunction "CC2_10") (pintype "input"))
    )
    (net (code "20") (name "Net-(USB2-CC1)") (class "Default")
      (node (ref "R10") (pin "1") (pinfunction "1_1") (pintype "input"))
      (node (ref "USB2") (pin "4") (pinfunction "CC1_4") (pintype "input"))
    )
    (net (code "21") (name "Net-(USB2-CC2)") (class "Default")
      (node (ref "R9") (pin "1") (pinfunction "1_1") (pintype "input"))
      (node (ref "USB2") (pin "10") (pinfunction "CC2_10") (pintype "input"))
    )
    (net (code "22") (name "OSC32_IN") (class "Default")
      (node (ref "C12") (pin "2") (pinfunction "2_2") (pintype "input"))
      (node (ref "H3") (pin "18") (pinfunction "18_18") (pintype "input"))
      (node (ref "U1") (pin "3") (pinfunction "PC14-OSC32_IN_3") (pintype "unspecified"))
      (node (ref "X1") (pin "1") (pinfunction "1_1") (pintype "input"))
    )
    (net (code "23") (name "OSC32_OUT") (class "Default")
      (node (ref "C13") (pin "2") (pinfunction "2_2") (pintype "input"))
      (node (ref "H3") (pin "17") (pinfunction "17_17") (pintype "input"))
      (node (ref "U1") (pin "4") (pinfunction "PC15-OSC32_OUT_4") (pintype "unspecified"))
      (node (ref "X1") (pin "2") (pinfunction "2_2") (pintype "input"))
    )
    (net (code "24") (name "OSC_IN") (class "Default")
      (node (ref "C11") (pin "1") (pinfunction "1_1") (pintype "input"))
      (node (ref "U1") (pin "5") (pinfunction "PD0-OSC_IN_5") (pintype "unspecified"))
      (node (ref "X2") (pin "1") (pinfunction "1_1") (pintype "input"))
    )
    (net (code "25") (name "OSC_OUT") (class "Default")
      (node (ref "C14") (pin "2") (pinfunction "2_2") (pintype "input"))
      (node (ref "U1") (pin "6") (pinfunction "PD1-OSC_OUT_6") (pintype "unspecified"))
      (node (ref "X2") (pin "3") (pinfunction "3_3") (pintype "input"))
    )
    (net (code "26") (name "PA0") (class "Default")
      (node (ref "H3") (pin "16") (pinfunction "16_16") (pintype "input"))
      (node (ref "U1") (pin "10") (pinfunction "PA0-WKUP_10") (pintype "unspecified"))
    )
    (net (code "27") (name "PA1") (class "Default")
      (node (ref "H3") (pin "15") (pinfunction "15_15") (pintype "input"))
      (node (ref "U1") (pin "11") (pinfunction "PA1_11") (pintype "unspecified"))
    )
    (net (code "28") (name "PA2") (class "Default")
      (node (ref "H3") (pin "14") (pinfunction "14_14") (pintype "input"))
      (node (ref "U1") (pin "12") (pinfunction "PA2_12") (pintype "unspecified"))
    )
    (net (code "29") (name "PA3") (class "Default")
      (node (ref "H3") (pin "13") (pinfunction "13_13") (pintype "input"))
      (node (ref "U1") (pin "13") (pinfunction "PA3_13") (pintype "unspecified"))
    )
    (net (code "30") (name "PA4") (class "Default")
      (node (ref "H3") (pin "12") (pinfunction "12_12") (pintype "input"))
      (node (ref "U1") (pin "14") (pinfunction "PA4_14") (pintype "unspecified"))
    )
    (net (code "31") (name "PA5") (class "Default")
      (node (ref "H3") (pin "11") (pinfunction "11_11") (pintype "input"))
      (node (ref "U1") (pin "15") (pinfunction "PA5_15") (pintype "unspecified"))
    )
    (net (code "32") (name "PA6") (class "Default")
      (node (ref "H3") (pin "10") (pinfunction "10_10") (pintype "input"))
      (node (ref "U1") (pin "16") (pinfunction "PA6_16") (pintype "unspecified"))
    )
    (net (code "33") (name "PA7") (class "Default")
      (node (ref "H3") (pin "9") (pinfunction "9_9") (pintype "input"))
      (node (ref "U1") (pin "17") (pinfunction "PA7_17") (pintype "unspecified"))
    )
    (net (code "34") (name "PA8") (class "Default")
      (node (ref "H4") (pin "16") (pinfunction "16_16") (pintype "input"))
      (node (ref "U1") (pin "29") (pinfunction "PA8_29") (pintype "unspecified"))
    )
    (net (code "35") (name "PA9{slash}USART1_TX") (class "Default")
      (node (ref "H4") (pin "15") (pinfunction "15_15") (pintype "input"))
      (node (ref "H6") (pin "2") (pinfunction "2_2") (pintype "unspecified"))
      (node (ref "U1") (pin "30") (pinfunction "PA9_30") (pintype "unspecified"))
    )
    (net (code "36") (name "PA10{slash}USART1_RX") (class "Default")
      (node (ref "H4") (pin "14") (pinfunction "14_14") (pintype "input"))
      (node (ref "H7") (pin "2") (pinfunction "2_2") (pintype "unspecified"))
      (node (ref "U1") (pin "31") (pinfunction "PA10_31") (pintype "unspecified"))
    )
    (net (code "37") (name "PA13{slash}SWDIO") (class "Default")
      (node (ref "H5") (pin "2") (pinfunction "2_2") (pintype "unspecified"))
      (node (ref "U1") (pin "34") (pinfunction "PA13_34") (pintype "unspecified"))
    )
    (net (code "38") (name "PA14{slash}SWCLK") (class "Default")
      (node (ref "H5") (pin "3") (pinfunction "3_3") (pintype "unspecified"))
      (node (ref "U1") (pin "37") (pinfunction "PA14_37") (pintype "unspecified"))
    )
    (net (code "39") (name "PA15") (class "Default")
      (node (ref "H4") (pin "11") (pinfunction "11_11") (pintype "input"))
      (node (ref "U1") (pin "38") (pinfunction "PA15_38") (pintype "unspecified"))
    )
    (net (code "40") (name "PB0") (class "Default")
      (node (ref "H3") (pin "8") (pinfunction "8_8") (pintype "input"))
      (node (ref "U1") (pin "18") (pinfunction "PB0_18") (pintype "unspecified"))
    )
    (net (code "41") (name "PB1") (class "Default")
      (node (ref "H3") (pin "7") (pinfunction "7_7") (pintype "input"))
      (node (ref "U1") (pin "19") (pinfunction "PB1_19") (pintype "unspecified"))
    )
    (net (code "42") (name "PB3") (class "Default")
      (node (ref "H4") (pin "10") (pinfunction "10_10") (pintype "input"))
      (node (ref "U1") (pin "39") (pinfunction "PB3_39") (pintype "unspecified"))
    )
    (net (code "43") (name "PB4") (class "Default")
      (node (ref "H4") (pin "9") (pinfunction "9_9") (pintype "input"))
      (node (ref "U1") (pin "40") (pinfunction "PB4_40") (pintype "unspecified"))
    )
    (net (code "44") (name "PB5") (class "Default")
      (node (ref "H4") (pin "8") (pinfunction "8_8") (pintype "input"))
      (node (ref "U1") (pin "41") (pinfunction "PB5_41") (pintype "unspecified"))
    )
    (net (code "45") (name "PB6") (class "Default")
      (node (ref "H4") (pin "7") (pinfunction "7_7") (pintype "input"))
      (node (ref "U1") (pin "42") (pinfunction "PB6_42") (pintype "unspecified"))
    )
    (net (code "46") (name "PB7") (class "Default")
      (node (ref "H4") (pin "6") (pinfunction "6_6") (pintype "input"))
      (node (ref "U1") (pin "43") (pinfunction "PB7_43") (pintype "unspecified"))
    )
    (net (code "47") (name "PB8") (class "Default")
      (node (ref "H4") (pin "5") (pinfunction "5_5") (pintype "input"))
      (node (ref "U1") (pin "45") (pinfunction "PB8_45") (pintype "unspecified"))
    )
    (net (code "48") (name "PB9") (class "Default")
      (node (ref "H4") (pin "4") (pinfunction "4_4") (pintype "input"))
      (node (ref "U1") (pin "46") (pinfunction "PB9_46") (pintype "unspecified"))
    )
    (net (code "49") (name "PB10") (class "Default")
      (node (ref "H3") (pin "6") (pinfunction "6_6") (pintype "input"))
      (node (ref "U1") (pin "21") (pinfunction "PB10_21") (pintype "unspecified"))
    )
    (net (code "50") (name "PB11") (class "Default")
      (node (ref "H3") (pin "5") (pinfunction "5_5") (pintype "input"))
      (node (ref "U1") (pin "22") (pinfunction "PB11_22") (pintype "unspecified"))
    )
    (net (code "51") (name "PB12") (class "Default")
      (node (ref "H4") (pin "20") (pinfunction "20_20") (pintype "input"))
      (node (ref "U1") (pin "25") (pinfunction "PB12_25") (pintype "unspecified"))
    )
    (net (code "52") (name "PB13") (class "Default")
      (node (ref "H4") (pin "19") (pinfunction "19_19") (pintype "input"))
      (node (ref "U1") (pin "26") (pinfunction "PB13_26") (pintype "unspecified"))
    )
    (net (code "53") (name "PB14") (class "Default")
      (node (ref "H4") (pin "18") (pinfunction "18_18") (pintype "input"))
      (node (ref "U1") (pin "27") (pinfunction "PB14_27") (pintype "unspecified"))
    )
    (net (code "54") (name "PB15") (class "Default")
      (node (ref "H4") (pin "17") (pinfunction "17_17") (pintype "input"))
      (node (ref "U1") (pin "28") (pinfunction "PB15_28") (pintype "unspecified"))
    )
    (net (code "55") (name "PC13") (class "Default")
      (node (ref "H3") (pin "19") (pinfunction "19_19") (pintype "input"))
      (node (ref "R17") (pin "2") (pinfunction "2_2") (pintype "input"))
      (node (ref "U1") (pin "2") (pinfunction "PC13-TAMPER-RTC_2") (pintype "unspecified"))
    )
    (net (code "56") (name "USB_D+_PA12") (class "Default")
      (node (ref "H4") (pin "12") (pinfunction "12_12") (pintype "input"))
      (node (ref "R16") (pin "1") (pinfunction "1_1") (pintype "unspecified"))
      (node (ref "U1") (pin "33") (pinfunction "PA12_33") (pintype "unspecified"))
      (node (ref "USB1") (pin "6") (pinfunction "DP1_6") (pintype "input"))
      (node (ref "USB1") (pin "8") (pinfunction "DP2_8") (pintype "input"))
    )
    (net (code "57") (name "USB_D-_PA11") (class "Default")
      (node (ref "H4") (pin "13") (pinfunction "13_13") (pintype "input"))
      (node (ref "U1") (pin "32") (pinfunction "PA11_32") (pintype "unspecified"))
      (node (ref "USB1") (pin "5") (pinfunction "DN2_5") (pintype "input"))
      (node (ref "USB1") (pin "7") (pinfunction "DN1_7") (pintype "input"))
    )
    (net (code "58") (name "VBAT") (class "Default")
      (node (ref "H3") (pin "20") (pinfunction "20_20") (pintype "input"))
      (node (ref "U1") (pin "1") (pinfunction "VBAT_1") (pintype "unspecified"))
    )
    (net (code "59") (name "VBUS_5V") (class "Default")
      (node (ref "F3") (pin "2") (pinfunction "2_2") (pintype "unspecified"))
      (node (ref "USB1") (pin "11") (pinfunction "VBUS_11") (pintype "input"))
      (node (ref "USB1") (pin "2") (pinfunction "VBUS_2") (pintype "input"))
      (node (ref "USB2") (pin "11") (pinfunction "VBUS_11") (pintype "input"))
      (node (ref "USB2") (pin "2") (pinfunction "VBUS_2") (pintype "input"))
    )
    (net (code "60") (name "unconnected-(H6-Pad3)") (class "Default")
      (node (ref "H6") (pin "3") (pinfunction "3_3") (pintype "unspecified+no_connect"))
    )
    (net (code "61") (name "unconnected-(H7-Pad3)") (class "Default")
      (node (ref "H7") (pin "3") (pinfunction "3_3") (pintype "unspecified+no_connect"))
    )
    (net (code "62") (name "unconnected-(LDO1-NC-Pad4)") (class "Default")
      (node (ref "LDO1") (pin "4") (pinfunction "NC_4") (pintype "input+no_connect"))
    )
    (net (code "63") (name "unconnected-(U2-CTS#-Pad5)") (class "Default")
      (node (ref "U2") (pin "5") (pinfunction "CTS#_5") (pintype "input+no_connect"))
    )
    (net (code "64") (name "unconnected-(U2-RTS#-Pad4)") (class "Default")
      (node (ref "U2") (pin "4") (pinfunction "RTS#_4") (pintype "input+no_connect"))
    )
    (net (code "65") (name "unconnected-(U2-TNOW-Pad6)") (class "Default")
      (node (ref "U2") (pin "6") (pinfunction "TNOW_6") (pintype "input+no_connect"))
    )
    (net (code "66") (name "unconnected-(USB1-SBU1-Pad9)") (class "Default")
      (node (ref "USB1") (pin "9") (pinfunction "SBU1_9") (pintype "input+no_connect"))
    )
    (net (code "67") (name "unconnected-(USB1-SBU2-Pad3)") (class "Default")
      (node (ref "USB1") (pin "3") (pinfunction "SBU2_3") (pintype "input+no_connect"))
    )
    (net (code "68") (name "unconnected-(USB2-SBU1-Pad9)") (class "Default")
      (node (ref "USB2") (pin "9") (pinfunction "SBU1_9") (pintype "input+no_connect"))
    )
    (net (code "69") (name "unconnected-(USB2-SBU2-Pad3)") (class "Default")
      (node (ref "USB2") (pin "3") (pinfunction "SBU2_3") (pintype "input+no_connect"))
    )
  )
)
